# led-cube.net
KiCad netlist of a schematic drawn in Altium Designer
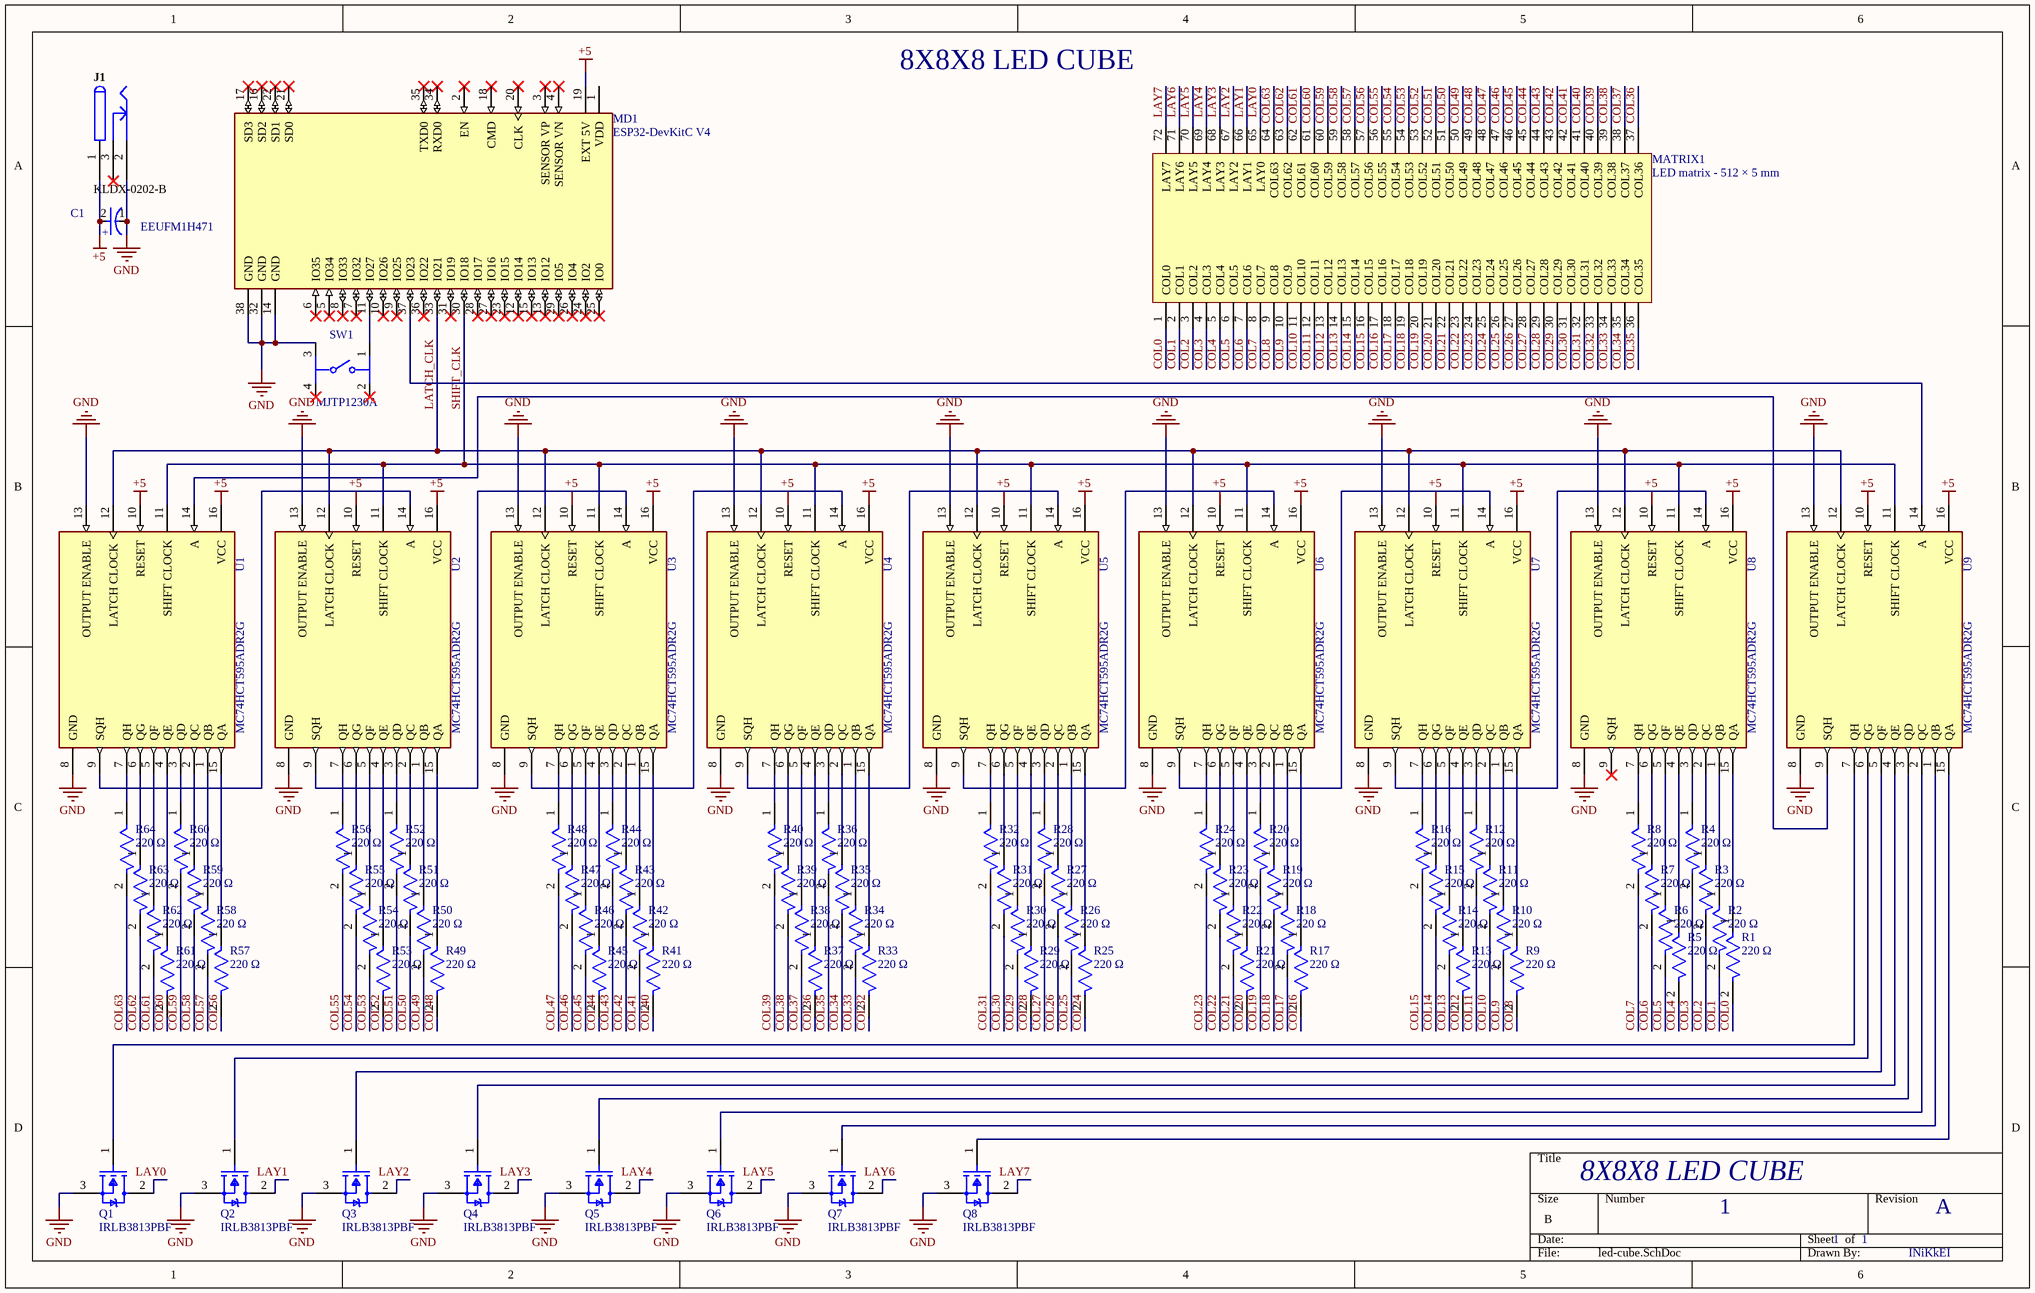
[diagram p0: led-cube.SchDoc]

(export (version "E")
  (design (tool "Eeschema 10.0.6"))
  (components
    (comp (ref "C1")
      (value "EEUFM1H471")
      (footprint "FP-RAD-TH-D_12_5_0_5-L_20-MFG")
      (description "Aluminum Electrolytic Capacitors (Radial Lead Type) 470uF ±20% 50V")
      (fields (field (name "TOLERANCE") "20%") (field (name "VOLTAGE") "50V"))
      (libsource (lib "Altium Content Vault") (part "a00bbbee19879c290e62620ae7e47b1"))
    )
    (comp (ref "J1")
      (value "KLDX-0202-B")
      (footprint "KYCN-KLDX-0202-B_V")
      (description "3 Conductor Power Jack, 2 break 2 aux contacts")
      (libsource (lib "Altium Content Vault") (part "KYCN-KLDX-0202-B-3"))
    )
    (comp (ref "MATRIX1")
      (value "LED matrix - 512 × 5 mm")
      (footprint "LED-MATRIX-8x8x8")
      (description "LED matrix - 512 × 5 mm - 8x8x8")
      (libsource (lib "led-cube") (part "LED-MATRIX"))
    )
    (comp (ref "MD1")
      (value "ESP32-DevKitC V4")
      (footprint "FP-ESP32-DevKitC_V4-MFG")
      (description "WiFi Development Tools (802.11) ESP32 General Development Kit, ESP32-WROOM-32 on the board")
      (fields
        (field (name "OCTOPART") "https://octopart.com/esp32-devkitc+v4-espressif+systems-107467262")
        (field (name "MANUFACTURER") "Espressif")
      )
      (libsource (lib "Altium Content Vault") (part "5ae961a1152c677524a60dea72d22f3"))
    )
    (comp (ref "Q1")
      (value "IRLB3813PBF")
      (footprint "FP-PG-TO220-3-MFG")
      (description "MOSFET N-CH 30V 260A TO-220AB")
      (fields
        (field (name "OCTOPART") "https://octopart.com/irlb3813pbf-infineon-65874923")
        (field (name "MANUFACTURER") "Infineon")
      )
      (libsource (lib "Altium Content Vault") (part "b09f7f152735e370c1ea22a33fa83d6"))
    )
    (comp (ref "Q2")
      (value "IRLB3813PBF")
      (footprint "FP-PG-TO220-3-MFG")
      (description "MOSFET N-CH 30V 260A TO-220AB")
      (fields
        (field (name "OCTOPART") "https://octopart.com/irlb3813pbf-infineon-65874923")
        (field (name "MANUFACTURER") "Infineon")
      )
      (libsource (lib "Altium Content Vault") (part "b09f7f152735e370c1ea22a33fa83d6"))
    )
    (comp (ref "Q3")
      (value "IRLB3813PBF")
      (footprint "FP-PG-TO220-3-MFG")
      (description "MOSFET N-CH 30V 260A TO-220AB")
      (fields
        (field (name "OCTOPART") "https://octopart.com/irlb3813pbf-infineon-65874923")
        (field (name "MANUFACTURER") "Infineon")
      )
      (libsource (lib "Altium Content Vault") (part "b09f7f152735e370c1ea22a33fa83d6"))
    )
    (comp (ref "Q4")
      (value "IRLB3813PBF")
      (footprint "FP-PG-TO220-3-MFG")
      (description "MOSFET N-CH 30V 260A TO-220AB")
      (fields
        (field (name "OCTOPART") "https://octopart.com/irlb3813pbf-infineon-65874923")
        (field (name "MANUFACTURER") "Infineon")
      )
      (libsource (lib "Altium Content Vault") (part "b09f7f152735e370c1ea22a33fa83d6"))
    )
    (comp (ref "Q5")
      (value "IRLB3813PBF")
      (footprint "FP-PG-TO220-3-MFG")
      (description "MOSFET N-CH 30V 260A TO-220AB")
      (fields
        (field (name "OCTOPART") "https://octopart.com/irlb3813pbf-infineon-65874923")
        (field (name "MANUFACTURER") "Infineon")
      )
      (libsource (lib "Altium Content Vault") (part "b09f7f152735e370c1ea22a33fa83d6"))
    )
    (comp (ref "Q6")
      (value "IRLB3813PBF")
      (footprint "FP-PG-TO220-3-MFG")
      (description "MOSFET N-CH 30V 260A TO-220AB")
      (fields
        (field (name "OCTOPART") "https://octopart.com/irlb3813pbf-infineon-65874923")
        (field (name "MANUFACTURER") "Infineon")
      )
      (libsource (lib "Altium Content Vault") (part "b09f7f152735e370c1ea22a33fa83d6"))
    )
    (comp (ref "Q7")
      (value "IRLB3813PBF")
      (footprint "FP-PG-TO220-3-MFG")
      (description "MOSFET N-CH 30V 260A TO-220AB")
      (fields
        (field (name "OCTOPART") "https://octopart.com/irlb3813pbf-infineon-65874923")
        (field (name "MANUFACTURER") "Infineon")
      )
      (libsource (lib "Altium Content Vault") (part "b09f7f152735e370c1ea22a33fa83d6"))
    )
    (comp (ref "Q8")
      (value "IRLB3813PBF")
      (footprint "FP-PG-TO220-3-MFG")
      (description "MOSFET N-CH 30V 260A TO-220AB")
      (fields
        (field (name "OCTOPART") "https://octopart.com/irlb3813pbf-infineon-65874923")
        (field (name "MANUFACTURER") "Infineon")
      )
      (libsource (lib "Altium Content Vault") (part "b09f7f152735e370c1ea22a33fa83d6"))
    )
    (comp (ref "R1")
      (value "220 Ω")
      (footprint "FP-MBA0204-MFG")
      (description "RES 220 OHM 0.4W 1% AXIAL")
      (fields
        (field (name "MANUFACTURER PART NUMBER") "MBA02040C2200FC100")
        (field (name "OCTOPART") "https://octopart.com/mba02040c2200fc100-vishay-43743094")
      )
      (libsource (lib "Altium Content Vault") (part "1029c3af85768c4190bb7ad29bc67b5"))
    )
    (comp (ref "R2")
      (value "220 Ω")
      (footprint "FP-MBA0204-MFG")
      (description "RES 220 OHM 0.4W 1% AXIAL")
      (fields
        (field (name "MANUFACTURER PART NUMBER") "MBA02040C2200FC100")
        (field (name "OCTOPART") "https://octopart.com/mba02040c2200fc100-vishay-43743094")
      )
      (libsource (lib "Altium Content Vault") (part "1029c3af85768c4190bb7ad29bc67b5"))
    )
    (comp (ref "R3")
      (value "220 Ω")
      (footprint "FP-MBA0204-MFG")
      (description "RES 220 OHM 0.4W 1% AXIAL")
      (fields
        (field (name "MANUFACTURER PART NUMBER") "MBA02040C2200FC100")
        (field (name "OCTOPART") "https://octopart.com/mba02040c2200fc100-vishay-43743094")
      )
      (libsource (lib "Altium Content Vault") (part "1029c3af85768c4190bb7ad29bc67b5"))
    )
    (comp (ref "R4")
      (value "220 Ω")
      (footprint "FP-MBA0204-MFG")
      (description "RES 220 OHM 0.4W 1% AXIAL")
      (fields
        (field (name "MANUFACTURER PART NUMBER") "MBA02040C2200FC100")
        (field (name "OCTOPART") "https://octopart.com/mba02040c2200fc100-vishay-43743094")
      )
      (libsource (lib "Altium Content Vault") (part "1029c3af85768c4190bb7ad29bc67b5"))
    )
    (comp (ref "R5")
      (value "220 Ω")
      (footprint "FP-MBA0204-MFG")
      (description "RES 220 OHM 0.4W 1% AXIAL")
      (fields
        (field (name "MANUFACTURER PART NUMBER") "MBA02040C2200FC100")
        (field (name "OCTOPART") "https://octopart.com/mba02040c2200fc100-vishay-43743094")
      )
      (libsource (lib "Altium Content Vault") (part "1029c3af85768c4190bb7ad29bc67b5"))
    )
    (comp (ref "R6")
      (value "220 Ω")
      (footprint "FP-MBA0204-MFG")
      (description "RES 220 OHM 0.4W 1% AXIAL")
      (fields
        (field (name "MANUFACTURER PART NUMBER") "MBA02040C2200FC100")
        (field (name "OCTOPART") "https://octopart.com/mba02040c2200fc100-vishay-43743094")
      )
      (libsource (lib "Altium Content Vault") (part "1029c3af85768c4190bb7ad29bc67b5"))
    )
    (comp (ref "R7")
      (value "220 Ω")
      (footprint "FP-MBA0204-MFG")
      (description "RES 220 OHM 0.4W 1% AXIAL")
      (fields
        (field (name "MANUFACTURER PART NUMBER") "MBA02040C2200FC100")
        (field (name "OCTOPART") "https://octopart.com/mba02040c2200fc100-vishay-43743094")
      )
      (libsource (lib "Altium Content Vault") (part "1029c3af85768c4190bb7ad29bc67b5"))
    )
    (comp (ref "R8")
      (value "220 Ω")
      (footprint "FP-MBA0204-MFG")
      (description "RES 220 OHM 0.4W 1% AXIAL")
      (fields
        (field (name "MANUFACTURER PART NUMBER") "MBA02040C2200FC100")
        (field (name "OCTOPART") "https://octopart.com/mba02040c2200fc100-vishay-43743094")
      )
      (libsource (lib "Altium Content Vault") (part "1029c3af85768c4190bb7ad29bc67b5"))
    )
    (comp (ref "R9")
      (value "220 Ω")
      (footprint "FP-MBA0204-MFG")
      (description "RES 220 OHM 0.4W 1% AXIAL")
      (fields
        (field (name "MANUFACTURER PART NUMBER") "MBA02040C2200FC100")
        (field (name "OCTOPART") "https://octopart.com/mba02040c2200fc100-vishay-43743094")
      )
      (libsource (lib "Altium Content Vault") (part "1029c3af85768c4190bb7ad29bc67b5"))
    )
    (comp (ref "R10")
      (value "220 Ω")
      (footprint "FP-MBA0204-MFG")
      (description "RES 220 OHM 0.4W 1% AXIAL")
      (fields
        (field (name "MANUFACTURER PART NUMBER") "MBA02040C2200FC100")
        (field (name "OCTOPART") "https://octopart.com/mba02040c2200fc100-vishay-43743094")
      )
      (libsource (lib "Altium Content Vault") (part "1029c3af85768c4190bb7ad29bc67b5"))
    )
    (comp (ref "R11")
      (value "220 Ω")
      (footprint "FP-MBA0204-MFG")
      (description "RES 220 OHM 0.4W 1% AXIAL")
      (fields
        (field (name "MANUFACTURER PART NUMBER") "MBA02040C2200FC100")
        (field (name "OCTOPART") "https://octopart.com/mba02040c2200fc100-vishay-43743094")
      )
      (libsource (lib "Altium Content Vault") (part "1029c3af85768c4190bb7ad29bc67b5"))
    )
    (comp (ref "R12")
      (value "220 Ω")
      (footprint "FP-MBA0204-MFG")
      (description "RES 220 OHM 0.4W 1% AXIAL")
      (fields
        (field (name "MANUFACTURER PART NUMBER") "MBA02040C2200FC100")
        (field (name "OCTOPART") "https://octopart.com/mba02040c2200fc100-vishay-43743094")
      )
      (libsource (lib "Altium Content Vault") (part "1029c3af85768c4190bb7ad29bc67b5"))
    )
    (comp (ref "R13")
      (value "220 Ω")
      (footprint "FP-MBA0204-MFG")
      (description "RES 220 OHM 0.4W 1% AXIAL")
      (fields
        (field (name "MANUFACTURER PART NUMBER") "MBA02040C2200FC100")
        (field (name "OCTOPART") "https://octopart.com/mba02040c2200fc100-vishay-43743094")
      )
      (libsource (lib "Altium Content Vault") (part "1029c3af85768c4190bb7ad29bc67b5"))
    )
    (comp (ref "R14")
      (value "220 Ω")
      (footprint "FP-MBA0204-MFG")
      (description "RES 220 OHM 0.4W 1% AXIAL")
      (fields
        (field (name "MANUFACTURER PART NUMBER") "MBA02040C2200FC100")
        (field (name "OCTOPART") "https://octopart.com/mba02040c2200fc100-vishay-43743094")
      )
      (libsource (lib "Altium Content Vault") (part "1029c3af85768c4190bb7ad29bc67b5"))
    )
    (comp (ref "R15")
      (value "220 Ω")
      (footprint "FP-MBA0204-MFG")
      (description "RES 220 OHM 0.4W 1% AXIAL")
      (fields
        (field (name "MANUFACTURER PART NUMBER") "MBA02040C2200FC100")
        (field (name "OCTOPART") "https://octopart.com/mba02040c2200fc100-vishay-43743094")
      )
      (libsource (lib "Altium Content Vault") (part "1029c3af85768c4190bb7ad29bc67b5"))
    )
    (comp (ref "R16")
      (value "220 Ω")
      (footprint "FP-MBA0204-MFG")
      (description "RES 220 OHM 0.4W 1% AXIAL")
      (fields
        (field (name "MANUFACTURER PART NUMBER") "MBA02040C2200FC100")
        (field (name "OCTOPART") "https://octopart.com/mba02040c2200fc100-vishay-43743094")
      )
      (libsource (lib "Altium Content Vault") (part "1029c3af85768c4190bb7ad29bc67b5"))
    )
    (comp (ref "R17")
      (value "220 Ω")
      (footprint "FP-MBA0204-MFG")
      (description "RES 220 OHM 0.4W 1% AXIAL")
      (fields
        (field (name "MANUFACTURER PART NUMBER") "MBA02040C2200FC100")
        (field (name "OCTOPART") "https://octopart.com/mba02040c2200fc100-vishay-43743094")
      )
      (libsource (lib "Altium Content Vault") (part "1029c3af85768c4190bb7ad29bc67b5"))
    )
    (comp (ref "R18")
      (value "220 Ω")
      (footprint "FP-MBA0204-MFG")
      (description "RES 220 OHM 0.4W 1% AXIAL")
      (fields
        (field (name "MANUFACTURER PART NUMBER") "MBA02040C2200FC100")
        (field (name "OCTOPART") "https://octopart.com/mba02040c2200fc100-vishay-43743094")
      )
      (libsource (lib "Altium Content Vault") (part "1029c3af85768c4190bb7ad29bc67b5"))
    )
    (comp (ref "R19")
      (value "220 Ω")
      (footprint "FP-MBA0204-MFG")
      (description "RES 220 OHM 0.4W 1% AXIAL")
      (fields
        (field (name "MANUFACTURER PART NUMBER") "MBA02040C2200FC100")
        (field (name "OCTOPART") "https://octopart.com/mba02040c2200fc100-vishay-43743094")
      )
      (libsource (lib "Altium Content Vault") (part "1029c3af85768c4190bb7ad29bc67b5"))
    )
    (comp (ref "R20")
      (value "220 Ω")
      (footprint "FP-MBA0204-MFG")
      (description "RES 220 OHM 0.4W 1% AXIAL")
      (fields
        (field (name "MANUFACTURER PART NUMBER") "MBA02040C2200FC100")
        (field (name "OCTOPART") "https://octopart.com/mba02040c2200fc100-vishay-43743094")
      )
      (libsource (lib "Altium Content Vault") (part "1029c3af85768c4190bb7ad29bc67b5"))
    )
    (comp (ref "R21")
      (value "220 Ω")
      (footprint "FP-MBA0204-MFG")
      (description "RES 220 OHM 0.4W 1% AXIAL")
      (fields
        (field (name "MANUFACTURER PART NUMBER") "MBA02040C2200FC100")
        (field (name "OCTOPART") "https://octopart.com/mba02040c2200fc100-vishay-43743094")
      )
      (libsource (lib "Altium Content Vault") (part "1029c3af85768c4190bb7ad29bc67b5"))
    )
    (comp (ref "R22")
      (value "220 Ω")
      (footprint "FP-MBA0204-MFG")
      (description "RES 220 OHM 0.4W 1% AXIAL")
      (fields
        (field (name "MANUFACTURER PART NUMBER") "MBA02040C2200FC100")
        (field (name "OCTOPART") "https://octopart.com/mba02040c2200fc100-vishay-43743094")
      )
      (libsource (lib "Altium Content Vault") (part "1029c3af85768c4190bb7ad29bc67b5"))
    )
    (comp (ref "R23")
      (value "220 Ω")
      (footprint "FP-MBA0204-MFG")
      (description "RES 220 OHM 0.4W 1% AXIAL")
      (fields
        (field (name "MANUFACTURER PART NUMBER") "MBA02040C2200FC100")
        (field (name "OCTOPART") "https://octopart.com/mba02040c2200fc100-vishay-43743094")
      )
      (libsource (lib "Altium Content Vault") (part "1029c3af85768c4190bb7ad29bc67b5"))
    )
    (comp (ref "R24")
      (value "220 Ω")
      (footprint "FP-MBA0204-MFG")
      (description "RES 220 OHM 0.4W 1% AXIAL")
      (fields
        (field (name "MANUFACTURER PART NUMBER") "MBA02040C2200FC100")
        (field (name "OCTOPART") "https://octopart.com/mba02040c2200fc100-vishay-43743094")
      )
      (libsource (lib "Altium Content Vault") (part "1029c3af85768c4190bb7ad29bc67b5"))
    )
    (comp (ref "R25")
      (value "220 Ω")
      (footprint "FP-MBA0204-MFG")
      (description "RES 220 OHM 0.4W 1% AXIAL")
      (fields
        (field (name "MANUFACTURER PART NUMBER") "MBA02040C2200FC100")
        (field (name "OCTOPART") "https://octopart.com/mba02040c2200fc100-vishay-43743094")
      )
      (libsource (lib "Altium Content Vault") (part "1029c3af85768c4190bb7ad29bc67b5"))
    )
    (comp (ref "R26")
      (value "220 Ω")
      (footprint "FP-MBA0204-MFG")
      (description "RES 220 OHM 0.4W 1% AXIAL")
      (fields
        (field (name "MANUFACTURER PART NUMBER") "MBA02040C2200FC100")
        (field (name "OCTOPART") "https://octopart.com/mba02040c2200fc100-vishay-43743094")
      )
      (libsource (lib "Altium Content Vault") (part "1029c3af85768c4190bb7ad29bc67b5"))
    )
    (comp (ref "R27")
      (value "220 Ω")
      (footprint "FP-MBA0204-MFG")
      (description "RES 220 OHM 0.4W 1% AXIAL")
      (fields
        (field (name "MANUFACTURER PART NUMBER") "MBA02040C2200FC100")
        (field (name "OCTOPART") "https://octopart.com/mba02040c2200fc100-vishay-43743094")
      )
      (libsource (lib "Altium Content Vault") (part "1029c3af85768c4190bb7ad29bc67b5"))
    )
    (comp (ref "R28")
      (value "220 Ω")
      (footprint "FP-MBA0204-MFG")
      (description "RES 220 OHM 0.4W 1% AXIAL")
      (fields
        (field (name "MANUFACTURER PART NUMBER") "MBA02040C2200FC100")
        (field (name "OCTOPART") "https://octopart.com/mba02040c2200fc100-vishay-43743094")
      )
      (libsource (lib "Altium Content Vault") (part "1029c3af85768c4190bb7ad29bc67b5"))
    )
    (comp (ref "R29")
      (value "220 Ω")
      (footprint "FP-MBA0204-MFG")
      (description "RES 220 OHM 0.4W 1% AXIAL")
      (fields
        (field (name "MANUFACTURER PART NUMBER") "MBA02040C2200FC100")
        (field (name "OCTOPART") "https://octopart.com/mba02040c2200fc100-vishay-43743094")
      )
      (libsource (lib "Altium Content Vault") (part "1029c3af85768c4190bb7ad29bc67b5"))
    )
    (comp (ref "R30")
      (value "220 Ω")
      (footprint "FP-MBA0204-MFG")
      (description "RES 220 OHM 0.4W 1% AXIAL")
      (fields
        (field (name "MANUFACTURER PART NUMBER") "MBA02040C2200FC100")
        (field (name "OCTOPART") "https://octopart.com/mba02040c2200fc100-vishay-43743094")
      )
      (libsource (lib "Altium Content Vault") (part "1029c3af85768c4190bb7ad29bc67b5"))
    )
    (comp (ref "R31")
      (value "220 Ω")
      (footprint "FP-MBA0204-MFG")
      (description "RES 220 OHM 0.4W 1% AXIAL")
      (fields
        (field (name "MANUFACTURER PART NUMBER") "MBA02040C2200FC100")
        (field (name "OCTOPART") "https://octopart.com/mba02040c2200fc100-vishay-43743094")
      )
      (libsource (lib "Altium Content Vault") (part "1029c3af85768c4190bb7ad29bc67b5"))
    )
    (comp (ref "R32")
      (value "220 Ω")
      (footprint "FP-MBA0204-MFG")
      (description "RES 220 OHM 0.4W 1% AXIAL")
      (fields
        (field (name "MANUFACTURER PART NUMBER") "MBA02040C2200FC100")
        (field (name "OCTOPART") "https://octopart.com/mba02040c2200fc100-vishay-43743094")
      )
      (libsource (lib "Altium Content Vault") (part "1029c3af85768c4190bb7ad29bc67b5"))
    )
    (comp (ref "R33")
      (value "220 Ω")
      (footprint "FP-MBA0204-MFG")
      (description "RES 220 OHM 0.4W 1% AXIAL")
      (fields
        (field (name "MANUFACTURER PART NUMBER") "MBA02040C2200FC100")
        (field (name "OCTOPART") "https://octopart.com/mba02040c2200fc100-vishay-43743094")
      )
      (libsource (lib "Altium Content Vault") (part "1029c3af85768c4190bb7ad29bc67b5"))
    )
    (comp (ref "R34")
      (value "220 Ω")
      (footprint "FP-MBA0204-MFG")
      (description "RES 220 OHM 0.4W 1% AXIAL")
      (fields
        (field (name "MANUFACTURER PART NUMBER") "MBA02040C2200FC100")
        (field (name "OCTOPART") "https://octopart.com/mba02040c2200fc100-vishay-43743094")
      )
      (libsource (lib "Altium Content Vault") (part "1029c3af85768c4190bb7ad29bc67b5"))
    )
    (comp (ref "R35")
      (value "220 Ω")
      (footprint "FP-MBA0204-MFG")
      (description "RES 220 OHM 0.4W 1% AXIAL")
      (fields
        (field (name "MANUFACTURER PART NUMBER") "MBA02040C2200FC100")
        (field (name "OCTOPART") "https://octopart.com/mba02040c2200fc100-vishay-43743094")
      )
      (libsource (lib "Altium Content Vault") (part "1029c3af85768c4190bb7ad29bc67b5"))
    )
    (comp (ref "R36")
      (value "220 Ω")
      (footprint "FP-MBA0204-MFG")
      (description "RES 220 OHM 0.4W 1% AXIAL")
      (fields
        (field (name "MANUFACTURER PART NUMBER") "MBA02040C2200FC100")
        (field (name "OCTOPART") "https://octopart.com/mba02040c2200fc100-vishay-43743094")
      )
      (libsource (lib "Altium Content Vault") (part "1029c3af85768c4190bb7ad29bc67b5"))
    )
    (comp (ref "R37")
      (value "220 Ω")
      (footprint "FP-MBA0204-MFG")
      (description "RES 220 OHM 0.4W 1% AXIAL")
      (fields
        (field (name "MANUFACTURER PART NUMBER") "MBA02040C2200FC100")
        (field (name "OCTOPART") "https://octopart.com/mba02040c2200fc100-vishay-43743094")
      )
      (libsource (lib "Altium Content Vault") (part "1029c3af85768c4190bb7ad29bc67b5"))
    )
    (comp (ref "R38")
      (value "220 Ω")
      (footprint "FP-MBA0204-MFG")
      (description "RES 220 OHM 0.4W 1% AXIAL")
      (fields
        (field (name "MANUFACTURER PART NUMBER") "MBA02040C2200FC100")
        (field (name "OCTOPART") "https://octopart.com/mba02040c2200fc100-vishay-43743094")
      )
      (libsource (lib "Altium Content Vault") (part "1029c3af85768c4190bb7ad29bc67b5"))
    )
    (comp (ref "R39")
      (value "220 Ω")
      (footprint "FP-MBA0204-MFG")
      (description "RES 220 OHM 0.4W 1% AXIAL")
      (fields
        (field (name "MANUFACTURER PART NUMBER") "MBA02040C2200FC100")
        (field (name "OCTOPART") "https://octopart.com/mba02040c2200fc100-vishay-43743094")
      )
      (libsource (lib "Altium Content Vault") (part "1029c3af85768c4190bb7ad29bc67b5"))
    )
    (comp (ref "R40")
      (value "220 Ω")
      (footprint "FP-MBA0204-MFG")
      (description "RES 220 OHM 0.4W 1% AXIAL")
      (fields
        (field (name "MANUFACTURER PART NUMBER") "MBA02040C2200FC100")
        (field (name "OCTOPART") "https://octopart.com/mba02040c2200fc100-vishay-43743094")
      )
      (libsource (lib "Altium Content Vault") (part "1029c3af85768c4190bb7ad29bc67b5"))
    )
    (comp (ref "R41")
      (value "220 Ω")
      (footprint "FP-MBA0204-MFG")
      (description "RES 220 OHM 0.4W 1% AXIAL")
      (fields
        (field (name "MANUFACTURER PART NUMBER") "MBA02040C2200FC100")
        (field (name "OCTOPART") "https://octopart.com/mba02040c2200fc100-vishay-43743094")
      )
      (libsource (lib "Altium Content Vault") (part "1029c3af85768c4190bb7ad29bc67b5"))
    )
    (comp (ref "R42")
      (value "220 Ω")
      (footprint "FP-MBA0204-MFG")
      (description "RES 220 OHM 0.4W 1% AXIAL")
      (fields
        (field (name "MANUFACTURER PART NUMBER") "MBA02040C2200FC100")
        (field (name "OCTOPART") "https://octopart.com/mba02040c2200fc100-vishay-43743094")
      )
      (libsource (lib "Altium Content Vault") (part "1029c3af85768c4190bb7ad29bc67b5"))
    )
    (comp (ref "R43")
      (value "220 Ω")
      (footprint "FP-MBA0204-MFG")
      (description "RES 220 OHM 0.4W 1% AXIAL")
      (fields
        (field (name "MANUFACTURER PART NUMBER") "MBA02040C2200FC100")
        (field (name "OCTOPART") "https://octopart.com/mba02040c2200fc100-vishay-43743094")
      )
      (libsource (lib "Altium Content Vault") (part "1029c3af85768c4190bb7ad29bc67b5"))
    )
    (comp (ref "R44")
      (value "220 Ω")
      (footprint "FP-MBA0204-MFG")
      (description "RES 220 OHM 0.4W 1% AXIAL")
      (fields
        (field (name "MANUFACTURER PART NUMBER") "MBA02040C2200FC100")
        (field (name "OCTOPART") "https://octopart.com/mba02040c2200fc100-vishay-43743094")
      )
      (libsource (lib "Altium Content Vault") (part "1029c3af85768c4190bb7ad29bc67b5"))
    )
    (comp (ref "R45")
      (value "220 Ω")
      (footprint "FP-MBA0204-MFG")
      (description "RES 220 OHM 0.4W 1% AXIAL")
      (fields
        (field (name "MANUFACTURER PART NUMBER") "MBA02040C2200FC100")
        (field (name "OCTOPART") "https://octopart.com/mba02040c2200fc100-vishay-43743094")
      )
      (libsource (lib "Altium Content Vault") (part "1029c3af85768c4190bb7ad29bc67b5"))
    )
    (comp (ref "R46")
      (value "220 Ω")
      (footprint "FP-MBA0204-MFG")
      (description "RES 220 OHM 0.4W 1% AXIAL")
      (fields
        (field (name "MANUFACTURER PART NUMBER") "MBA02040C2200FC100")
        (field (name "OCTOPART") "https://octopart.com/mba02040c2200fc100-vishay-43743094")
      )
      (libsource (lib "Altium Content Vault") (part "1029c3af85768c4190bb7ad29bc67b5"))
    )
    (comp (ref "R47")
      (value "220 Ω")
      (footprint "FP-MBA0204-MFG")
      (description "RES 220 OHM 0.4W 1% AXIAL")
      (fields
        (field (name "MANUFACTURER PART NUMBER") "MBA02040C2200FC100")
        (field (name "OCTOPART") "https://octopart.com/mba02040c2200fc100-vishay-43743094")
      )
      (libsource (lib "Altium Content Vault") (part "1029c3af85768c4190bb7ad29bc67b5"))
    )
    (comp (ref "R48")
      (value "220 Ω")
      (footprint "FP-MBA0204-MFG")
      (description "RES 220 OHM 0.4W 1% AXIAL")
      (fields
        (field (name "MANUFACTURER PART NUMBER") "MBA02040C2200FC100")
        (field (name "OCTOPART") "https://octopart.com/mba02040c2200fc100-vishay-43743094")
      )
      (libsource (lib "Altium Content Vault") (part "1029c3af85768c4190bb7ad29bc67b5"))
    )
    (comp (ref "R49")
      (value "220 Ω")
      (footprint "FP-MBA0204-MFG")
      (description "RES 220 OHM 0.4W 1% AXIAL")
      (fields
        (field (name "MANUFACTURER PART NUMBER") "MBA02040C2200FC100")
        (field (name "OCTOPART") "https://octopart.com/mba02040c2200fc100-vishay-43743094")
      )
      (libsource (lib "Altium Content Vault") (part "1029c3af85768c4190bb7ad29bc67b5"))
    )
    (comp (ref "R50")
      (value "220 Ω")
      (footprint "FP-MBA0204-MFG")
      (description "RES 220 OHM 0.4W 1% AXIAL")
      (fields
        (field (name "MANUFACTURER PART NUMBER") "MBA02040C2200FC100")
        (field (name "OCTOPART") "https://octopart.com/mba02040c2200fc100-vishay-43743094")
      )
      (libsource (lib "Altium Content Vault") (part "1029c3af85768c4190bb7ad29bc67b5"))
    )
    (comp (ref "R51")
      (value "220 Ω")
      (footprint "FP-MBA0204-MFG")
      (description "RES 220 OHM 0.4W 1% AXIAL")
      (fields
        (field (name "MANUFACTURER PART NUMBER") "MBA02040C2200FC100")
        (field (name "OCTOPART") "https://octopart.com/mba02040c2200fc100-vishay-43743094")
      )
      (libsource (lib "Altium Content Vault") (part "1029c3af85768c4190bb7ad29bc67b5"))
    )
    (comp (ref "R52")
      (value "220 Ω")
      (footprint "FP-MBA0204-MFG")
      (description "RES 220 OHM 0.4W 1% AXIAL")
      (fields
        (field (name "MANUFACTURER PART NUMBER") "MBA02040C2200FC100")
        (field (name "OCTOPART") "https://octopart.com/mba02040c2200fc100-vishay-43743094")
      )
      (libsource (lib "Altium Content Vault") (part "1029c3af85768c4190bb7ad29bc67b5"))
    )
    (comp (ref "R53")
      (value "220 Ω")
      (footprint "FP-MBA0204-MFG")
      (description "RES 220 OHM 0.4W 1% AXIAL")
      (fields
        (field (name "MANUFACTURER PART NUMBER") "MBA02040C2200FC100")
        (field (name "OCTOPART") "https://octopart.com/mba02040c2200fc100-vishay-43743094")
      )
      (libsource (lib "Altium Content Vault") (part "1029c3af85768c4190bb7ad29bc67b5"))
    )
    (comp (ref "R54")
      (value "220 Ω")
      (footprint "FP-MBA0204-MFG")
      (description "RES 220 OHM 0.4W 1% AXIAL")
      (fields
        (field (name "MANUFACTURER PART NUMBER") "MBA02040C2200FC100")
        (field (name "OCTOPART") "https://octopart.com/mba02040c2200fc100-vishay-43743094")
      )
      (libsource (lib "Altium Content Vault") (part "1029c3af85768c4190bb7ad29bc67b5"))
    )
    (comp (ref "R55")
      (value "220 Ω")
      (footprint "FP-MBA0204-MFG")
      (description "RES 220 OHM 0.4W 1% AXIAL")
      (fields
        (field (name "MANUFACTURER PART NUMBER") "MBA02040C2200FC100")
        (field (name "OCTOPART") "https://octopart.com/mba02040c2200fc100-vishay-43743094")
      )
      (libsource (lib "Altium Content Vault") (part "1029c3af85768c4190bb7ad29bc67b5"))
    )
    (comp (ref "R56")
      (value "220 Ω")
      (footprint "FP-MBA0204-MFG")
      (description "RES 220 OHM 0.4W 1% AXIAL")
      (fields
        (field (name "MANUFACTURER PART NUMBER") "MBA02040C2200FC100")
        (field (name "OCTOPART") "https://octopart.com/mba02040c2200fc100-vishay-43743094")
      )
      (libsource (lib "Altium Content Vault") (part "1029c3af85768c4190bb7ad29bc67b5"))
    )
    (comp (ref "R57")
      (value "220 Ω")
      (footprint "FP-MBA0204-MFG")
      (description "RES 220 OHM 0.4W 1% AXIAL")
      (fields
        (field (name "MANUFACTURER PART NUMBER") "MBA02040C2200FC100")
        (field (name "OCTOPART") "https://octopart.com/mba02040c2200fc100-vishay-43743094")
      )
      (libsource (lib "Altium Content Vault") (part "1029c3af85768c4190bb7ad29bc67b5"))
    )
    (comp (ref "R58")
      (value "220 Ω")
      (footprint "FP-MBA0204-MFG")
      (description "RES 220 OHM 0.4W 1% AXIAL")
      (fields
        (field (name "MANUFACTURER PART NUMBER") "MBA02040C2200FC100")
        (field (name "OCTOPART") "https://octopart.com/mba02040c2200fc100-vishay-43743094")
      )
      (libsource (lib "Altium Content Vault") (part "1029c3af85768c4190bb7ad29bc67b5"))
    )
    (comp (ref "R59")
      (value "220 Ω")
      (footprint "FP-MBA0204-MFG")
      (description "RES 220 OHM 0.4W 1% AXIAL")
      (fields
        (field (name "MANUFACTURER PART NUMBER") "MBA02040C2200FC100")
        (field (name "OCTOPART") "https://octopart.com/mba02040c2200fc100-vishay-43743094")
      )
      (libsource (lib "Altium Content Vault") (part "1029c3af85768c4190bb7ad29bc67b5"))
    )
    (comp (ref "R60")
      (value "220 Ω")
      (footprint "FP-MBA0204-MFG")
      (description "RES 220 OHM 0.4W 1% AXIAL")
      (fields
        (field (name "MANUFACTURER PART NUMBER") "MBA02040C2200FC100")
        (field (name "OCTOPART") "https://octopart.com/mba02040c2200fc100-vishay-43743094")
      )
      (libsource (lib "Altium Content Vault") (part "1029c3af85768c4190bb7ad29bc67b5"))
    )
    (comp (ref "R61")
      (value "220 Ω")
      (footprint "FP-MBA0204-MFG")
      (description "RES 220 OHM 0.4W 1% AXIAL")
      (fields
        (field (name "MANUFACTURER PART NUMBER") "MBA02040C2200FC100")
        (field (name "OCTOPART") "https://octopart.com/mba02040c2200fc100-vishay-43743094")
      )
      (libsource (lib "Altium Content Vault") (part "1029c3af85768c4190bb7ad29bc67b5"))
    )
    (comp (ref "R62")
      (value "220 Ω")
      (footprint "FP-MBA0204-MFG")
      (description "RES 220 OHM 0.4W 1% AXIAL")
      (fields
        (field (name "MANUFACTURER PART NUMBER") "MBA02040C2200FC100")
        (field (name "OCTOPART") "https://octopart.com/mba02040c2200fc100-vishay-43743094")
      )
      (libsource (lib "Altium Content Vault") (part "1029c3af85768c4190bb7ad29bc67b5"))
    )
    (comp (ref "R63")
      (value "220 Ω")
      (footprint "FP-MBA0204-MFG")
      (description "RES 220 OHM 0.4W 1% AXIAL")
      (fields
        (field (name "MANUFACTURER PART NUMBER") "MBA02040C2200FC100")
        (field (name "OCTOPART") "https://octopart.com/mba02040c2200fc100-vishay-43743094")
      )
      (libsource (lib "Altium Content Vault") (part "1029c3af85768c4190bb7ad29bc67b5"))
    )
    (comp (ref "R64")
      (value "220 Ω")
      (footprint "FP-MBA0204-MFG")
      (description "RES 220 OHM 0.4W 1% AXIAL")
      (fields
        (field (name "MANUFACTURER PART NUMBER") "MBA02040C2200FC100")
        (field (name "OCTOPART") "https://octopart.com/mba02040c2200fc100-vishay-43743094")
      )
      (libsource (lib "Altium Content Vault") (part "1029c3af85768c4190bb7ad29bc67b5"))
    )
    (comp (ref "SW1")
      (value "MJTP1230A")
      (footprint "FP-MJTP1230A-MFG")
      (description "SWITCH TACTILE SPST-NO 0.05A 12V")
      (libsource (lib "Altium Content Vault") (part "1adf0dd01260c80cf25a44bfd6b99ba"))
    )
    (comp (ref "U1")
      (value "MC74HCT595ADR2G")
      (footprint "FP-751B-05-MFG")
      (libsource (lib "Altium Content Vault") (part "355c601ec69527b18b491ba11f96b67"))
    )
    (comp (ref "U2")
      (value "MC74HCT595ADR2G")
      (footprint "FP-751B-05-MFG")
      (libsource (lib "Altium Content Vault") (part "355c601ec69527b18b491ba11f96b67"))
    )
    (comp (ref "U3")
      (value "MC74HCT595ADR2G")
      (footprint "FP-751B-05-MFG")
      (libsource (lib "Altium Content Vault") (part "355c601ec69527b18b491ba11f96b67"))
    )
    (comp (ref "U4")
      (value "MC74HCT595ADR2G")
      (footprint "FP-751B-05-MFG")
      (libsource (lib "Altium Content Vault") (part "355c601ec69527b18b491ba11f96b67"))
    )
    (comp (ref "U5")
      (value "MC74HCT595ADR2G")
      (footprint "FP-751B-05-MFG")
      (libsource (lib "Altium Content Vault") (part "355c601ec69527b18b491ba11f96b67"))
    )
    (comp (ref "U6")
      (value "MC74HCT595ADR2G")
      (footprint "FP-751B-05-MFG")
      (libsource (lib "Altium Content Vault") (part "355c601ec69527b18b491ba11f96b67"))
    )
    (comp (ref "U7")
      (value "MC74HCT595ADR2G")
      (footprint "FP-751B-05-MFG")
      (libsource (lib "Altium Content Vault") (part "355c601ec69527b18b491ba11f96b67"))
    )
    (comp (ref "U8")
      (value "MC74HCT595ADR2G")
      (footprint "FP-751B-05-MFG")
      (libsource (lib "Altium Content Vault") (part "355c601ec69527b18b491ba11f96b67"))
    )
    (comp (ref "U9")
      (value "MC74HCT595ADR2G")
      (footprint "FP-751B-05-MFG")
      (libsource (lib "Altium Content Vault") (part "355c601ec69527b18b491ba11f96b67"))
    )
  )
  (nets
    (net (code "1") (name "+5") (class "Default")
      (node (ref "C1") (pin "2") (pinfunction "A_2") (pintype "passive"))
      (node (ref "J1") (pin "1") (pintype "power_in"))
      (node (ref "MD1") (pin "19") (pinfunction "EXT_5V_19") (pintype "power_in"))
      (node (ref "U1") (pin "10") (pinfunction "RESET_10") (pintype "input"))
      (node (ref "U1") (pin "16") (pinfunction "VCC_16") (pintype "power_in"))
      (node (ref "U2") (pin "10") (pinfunction "RESET_10") (pintype "input"))
      (node (ref "U2") (pin "16") (pinfunction "VCC_16") (pintype "power_in"))
      (node (ref "U3") (pin "10") (pinfunction "RESET_10") (pintype "input"))
      (node (ref "U3") (pin "16") (pinfunction "VCC_16") (pintype "power_in"))
      (node (ref "U4") (pin "10") (pinfunction "RESET_10") (pintype "input"))
      (node (ref "U4") (pin "16") (pinfunction "VCC_16") (pintype "power_in"))
      (node (ref "U5") (pin "10") (pinfunction "RESET_10") (pintype "input"))
      (node (ref "U5") (pin "16") (pinfunction "VCC_16") (pintype "power_in"))
      (node (ref "U6") (pin "10") (pinfunction "RESET_10") (pintype "input"))
      (node (ref "U6") (pin "16") (pinfunction "VCC_16") (pintype "power_in"))
      (node (ref "U7") (pin "10") (pinfunction "RESET_10") (pintype "input"))
      (node (ref "U7") (pin "16") (pinfunction "VCC_16") (pintype "power_in"))
      (node (ref "U8") (pin "10") (pinfunction "RESET_10") (pintype "input"))
      (node (ref "U8") (pin "16") (pinfunction "VCC_16") (pintype "power_in"))
      (node (ref "U9") (pin "10") (pinfunction "RESET_10") (pintype "input"))
      (node (ref "U9") (pin "16") (pinfunction "VCC_16") (pintype "power_in"))
    )
    (net (code "2") (name "/COL0") (class "Default")
      (node (ref "MATRIX1") (pin "1") (pinfunction "COL0_1") (pintype "passive"))
      (node (ref "R1") (pin "2") (pinfunction "2_2") (pintype "passive"))
    )
    (net (code "3") (name "/COL1") (class "Default")
      (node (ref "MATRIX1") (pin "2") (pinfunction "COL1_2") (pintype "passive"))
      (node (ref "R2") (pin "2") (pinfunction "2_2") (pintype "passive"))
    )
    (net (code "4") (name "/COL2") (class "Default")
      (node (ref "MATRIX1") (pin "3") (pinfunction "COL2_3") (pintype "passive"))
      (node (ref "R3") (pin "2") (pinfunction "2_2") (pintype "passive"))
    )
    (net (code "5") (name "/COL3") (class "Default")
      (node (ref "MATRIX1") (pin "4") (pinfunction "COL3_4") (pintype "passive"))
      (node (ref "R4") (pin "2") (pinfunction "2_2") (pintype "passive"))
    )
    (net (code "6") (name "/COL4") (class "Default")
      (node (ref "MATRIX1") (pin "5") (pinfunction "COL4_5") (pintype "passive"))
      (node (ref "R5") (pin "2") (pinfunction "2_2") (pintype "passive"))
    )
    (net (code "7") (name "/COL5") (class "Default")
      (node (ref "MATRIX1") (pin "6") (pinfunction "COL5_6") (pintype "passive"))
      (node (ref "R6") (pin "2") (pinfunction "2_2") (pintype "passive"))
    )
    (net (code "8") (name "/COL6") (class "Default")
      (node (ref "MATRIX1") (pin "7") (pinfunction "COL6_7") (pintype "passive"))
      (node (ref "R7") (pin "2") (pinfunction "2_2") (pintype "passive"))
    )
    (net (code "9") (name "/COL7") (class "Default")
      (node (ref "MATRIX1") (pin "8") (pinfunction "COL7_8") (pintype "passive"))
      (node (ref "R8") (pin "2") (pinfunction "2_2") (pintype "passive"))
    )
    (net (code "10") (name "/COL8") (class "Default")
      (node (ref "MATRIX1") (pin "9") (pinfunction "COL8_9") (pintype "passive"))
      (node (ref "R9") (pin "2") (pinfunction "2_2") (pintype "passive"))
    )
    (net (code "11") (name "/COL9") (class "Default")
      (node (ref "MATRIX1") (pin "10") (pinfunction "COL9_10") (pintype "passive"))
      (node (ref "R10") (pin "2") (pinfunction "2_2") (pintype "passive"))
    )
    (net (code "12") (name "/COL10") (class "Default")
      (node (ref "MATRIX1") (pin "11") (pinfunction "COL10_11") (pintype "passive"))
      (node (ref "R11") (pin "2") (pinfunction "2_2") (pintype "passive"))
    )
    (net (code "13") (name "/COL11") (class "Default")
      (node (ref "MATRIX1") (pin "12") (pinfunction "COL11_12") (pintype "passive"))
      (node (ref "R12") (pin "2") (pinfunction "2_2") (pintype "passive"))
    )
    (net (code "14") (name "/COL12") (class "Default")
      (node (ref "MATRIX1") (pin "13") (pinfunction "COL12_13") (pintype "passive"))
      (node (ref "R13") (pin "2") (pinfunction "2_2") (pintype "passive"))
    )
    (net (code "15") (name "/COL13") (class "Default")
      (node (ref "MATRIX1") (pin "14") (pinfunction "COL13_14") (pintype "passive"))
      (node (ref "R14") (pin "2") (pinfunction "2_2") (pintype "passive"))
    )
    (net (code "16") (name "/COL14") (class "Default")
      (node (ref "MATRIX1") (pin "15") (pinfunction "COL14_15") (pintype "passive"))
      (node (ref "R15") (pin "2") (pinfunction "2_2") (pintype "passive"))
    )
    (net (code "17") (name "/COL15") (class "Default")
      (node (ref "MATRIX1") (pin "16") (pinfunction "COL15_16") (pintype "passive"))
      (node (ref "R16") (pin "2") (pinfunction "2_2") (pintype "passive"))
    )
    (net (code "18") (name "/COL16") (class "Default")
      (node (ref "MATRIX1") (pin "17") (pinfunction "COL16_17") (pintype "passive"))
      (node (ref "R17") (pin "2") (pinfunction "2_2") (pintype "passive"))
    )
    (net (code "19") (name "/COL17") (class "Default")
      (node (ref "MATRIX1") (pin "18") (pinfunction "COL17_18") (pintype "passive"))
      (node (ref "R18") (pin "2") (pinfunction "2_2") (pintype "passive"))
    )
    (net (code "20") (name "/COL18") (class "Default")
      (node (ref "MATRIX1") (pin "19") (pinfunction "COL18_19") (pintype "passive"))
      (node (ref "R19") (pin "2") (pinfunction "2_2") (pintype "passive"))
    )
    (net (code "21") (name "/COL19") (class "Default")
      (node (ref "MATRIX1") (pin "20") (pinfunction "COL19_20") (pintype "passive"))
      (node (ref "R20") (pin "2") (pinfunction "2_2") (pintype "passive"))
    )
    (net (code "22") (name "/COL20") (class "Default")
      (node (ref "MATRIX1") (pin "21") (pinfunction "COL20_21") (pintype "passive"))
      (node (ref "R21") (pin "2") (pinfunction "2_2") (pintype "passive"))
    )
    (net (code "23") (name "/COL21") (class "Default")
      (node (ref "MATRIX1") (pin "22") (pinfunction "COL21_22") (pintype "passive"))
      (node (ref "R22") (pin "2") (pinfunction "2_2") (pintype "passive"))
    )
    (net (code "24") (name "/COL22") (class "Default")
      (node (ref "MATRIX1") (pin "23") (pinfunction "COL22_23") (pintype "passive"))
      (node (ref "R23") (pin "2") (pinfunction "2_2") (pintype "passive"))
    )
    (net (code "25") (name "/COL23") (class "Default")
      (node (ref "MATRIX1") (pin "24") (pinfunction "COL23_24") (pintype "passive"))
      (node (ref "R24") (pin "2") (pinfunction "2_2") (pintype "passive"))
    )
    (net (code "26") (name "/COL24") (class "Default")
      (node (ref "MATRIX1") (pin "25") (pinfunction "COL24_25") (pintype "passive"))
      (node (ref "R25") (pin "2") (pinfunction "2_2") (pintype "passive"))
    )
    (net (code "27") (name "/COL25") (class "Default")
      (node (ref "MATRIX1") (pin "26") (pinfunction "COL25_26") (pintype "passive"))
      (node (ref "R26") (pin "2") (pinfunction "2_2") (pintype "passive"))
    )
    (net (code "28") (name "/COL26") (class "Default")
      (node (ref "MATRIX1") (pin "27") (pinfunction "COL26_27") (pintype "passive"))
      (node (ref "R27") (pin "2") (pinfunction "2_2") (pintype "passive"))
    )
    (net (code "29") (name "/COL27") (class "Default")
      (node (ref "MATRIX1") (pin "28") (pinfunction "COL27_28") (pintype "passive"))
      (node (ref "R28") (pin "2") (pinfunction "2_2") (pintype "passive"))
    )
    (net (code "30") (name "/COL28") (class "Default")
      (node (ref "MATRIX1") (pin "29") (pinfunction "COL28_29") (pintype "passive"))
      (node (ref "R29") (pin "2") (pinfunction "2_2") (pintype "passive"))
    )
    (net (code "31") (name "/COL29") (class "Default")
      (node (ref "MATRIX1") (pin "30") (pinfunction "COL29_30") (pintype "passive"))
      (node (ref "R30") (pin "2") (pinfunction "2_2") (pintype "passive"))
    )
    (net (code "32") (name "/COL30") (class "Default")
      (node (ref "MATRIX1") (pin "31") (pinfunction "COL30_31") (pintype "passive"))
      (node (ref "R31") (pin "2") (pinfunction "2_2") (pintype "passive"))
    )
    (net (code "33") (name "/COL31") (class "Default")
      (node (ref "MATRIX1") (pin "32") (pinfunction "COL31_32") (pintype "passive"))
      (node (ref "R32") (pin "2") (pinfunction "2_2") (pintype "passive"))
    )
    (net (code "34") (name "/COL32") (class "Default")
      (node (ref "MATRIX1") (pin "33") (pinfunction "COL32_33") (pintype "passive"))
      (node (ref "R33") (pin "2") (pinfunction "2_2") (pintype "passive"))
    )
    (net (code "35") (name "/COL33") (class "Default")
      (node (ref "MATRIX1") (pin "34") (pinfunction "COL33_34") (pintype "passive"))
      (node (ref "R34") (pin "2") (pinfunction "2_2") (pintype "passive"))
    )
    (net (code "36") (name "/COL34") (class "Default")
      (node (ref "MATRIX1") (pin "35") (pinfunction "COL34_35") (pintype "passive"))
      (node (ref "R35") (pin "2") (pinfunction "2_2") (pintype "passive"))
    )
    (net (code "37") (name "/COL35") (class "Default")
      (node (ref "MATRIX1") (pin "36") (pinfunction "COL35_36") (pintype "passive"))
      (node (ref "R36") (pin "2") (pinfunction "2_2") (pintype "passive"))
    )
    (net (code "38") (name "/COL36") (class "Default")
      (node (ref "MATRIX1") (pin "37") (pinfunction "COL36_37") (pintype "passive"))
      (node (ref "R37") (pin "2") (pinfunction "2_2") (pintype "passive"))
    )
    (net (code "39") (name "/COL37") (class "Default")
      (node (ref "MATRIX1") (pin "38") (pinfunction "COL37_38") (pintype "passive"))
      (node (ref "R38") (pin "2") (pinfunction "2_2") (pintype "passive"))
    )
    (net (code "40") (name "/COL38") (class "Default")
      (node (ref "MATRIX1") (pin "39") (pinfunction "COL38_39") (pintype "passive"))
      (node (ref "R39") (pin "2") (pinfunction "2_2") (pintype "passive"))
    )
    (net (code "41") (name "/COL39") (class "Default")
      (node (ref "MATRIX1") (pin "40") (pinfunction "COL39_40") (pintype "passive"))
      (node (ref "R40") (pin "2") (pinfunction "2_2") (pintype "passive"))
    )
    (net (code "42") (name "/COL40") (class "Default")
      (node (ref "MATRIX1") (pin "41") (pinfunction "COL40_41") (pintype "passive"))
      (node (ref "R41") (pin "2") (pinfunction "2_2") (pintype "passive"))
    )
    (net (code "43") (name "/COL41") (class "Default")
      (node (ref "MATRIX1") (pin "42") (pinfunction "COL41_42") (pintype "passive"))
      (node (ref "R42") (pin "2") (pinfunction "2_2") (pintype "passive"))
    )
    (net (code "44") (name "/COL42") (class "Default")
      (node (ref "MATRIX1") (pin "43") (pinfunction "COL42_43") (pintype "passive"))
      (node (ref "R43") (pin "2") (pinfunction "2_2") (pintype "passive"))
    )
    (net (code "45") (name "/COL43") (class "Default")
      (node (ref "MATRIX1") (pin "44") (pinfunction "COL43_44") (pintype "passive"))
      (node (ref "R44") (pin "2") (pinfunction "2_2") (pintype "passive"))
    )
    (net (code "46") (name "/COL44") (class "Default")
      (node (ref "MATRIX1") (pin "45") (pinfunction "COL44_45") (pintype "passive"))
      (node (ref "R45") (pin "2") (pinfunction "2_2") (pintype "passive"))
    )
    (net (code "47") (name "/COL45") (class "Default")
      (node (ref "MATRIX1") (pin "46") (pinfunction "COL45_46") (pintype "passive"))
      (node (ref "R46") (pin "2") (pinfunction "2_2") (pintype "passive"))
    )
    (net (code "48") (name "/COL46") (class "Default")
      (node (ref "MATRIX1") (pin "47") (pinfunction "COL46_47") (pintype "passive"))
      (node (ref "R47") (pin "2") (pinfunction "2_2") (pintype "passive"))
    )
    (net (code "49") (name "/COL47") (class "Default")
      (node (ref "MATRIX1") (pin "48") (pinfunction "COL47_48") (pintype "passive"))
      (node (ref "R48") (pin "2") (pinfunction "2_2") (pintype "passive"))
    )
    (net (code "50") (name "/COL48") (class "Default")
      (node (ref "MATRIX1") (pin "49") (pinfunction "COL48_49") (pintype "passive"))
      (node (ref "R49") (pin "2") (pinfunction "2_2") (pintype "passive"))
    )
    (net (code "51") (name "/COL49") (class "Default")
      (node (ref "MATRIX1") (pin "50") (pinfunction "COL49_50") (pintype "passive"))
      (node (ref "R50") (pin "2") (pinfunction "2_2") (pintype "passive"))
    )
    (net (code "52") (name "/COL50") (class "Default")
      (node (ref "MATRIX1") (pin "51") (pinfunction "COL50_51") (pintype "passive"))
      (node (ref "R51") (pin "2") (pinfunction "2_2") (pintype "passive"))
    )
    (net (code "53") (name "/COL51") (class "Default")
      (node (ref "MATRIX1") (pin "52") (pinfunction "COL51_52") (pintype "passive"))
      (node (ref "R52") (pin "2") (pinfunction "2_2") (pintype "passive"))
    )
    (net (code "54") (name "/COL52") (class "Default")
      (node (ref "MATRIX1") (pin "53") (pinfunction "COL52_53") (pintype "passive"))
      (node (ref "R53") (pin "2") (pinfunction "2_2") (pintype "passive"))
    )
    (net (code "55") (name "/COL53") (class "Default")
      (node (ref "MATRIX1") (pin "54") (pinfunction "COL53_54") (pintype "passive"))
      (node (ref "R54") (pin "2") (pinfunction "2_2") (pintype "passive"))
    )
    (net (code "56") (name "/COL54") (class "Default")
      (node (ref "MATRIX1") (pin "55") (pinfunction "COL54_55") (pintype "passive"))
      (node (ref "R55") (pin "2") (pinfunction "2_2") (pintype "passive"))
    )
    (net (code "57") (name "/COL55") (class "Default")
      (node (ref "MATRIX1") (pin "56") (pinfunction "COL55_56") (pintype "passive"))
      (node (ref "R56") (pin "2") (pinfunction "2_2") (pintype "passive"))
    )
    (net (code "58") (name "/COL56") (class "Default")
      (node (ref "MATRIX1") (pin "57") (pinfunction "COL56_57") (pintype "passive"))
      (node (ref "R57") (pin "2") (pinfunction "2_2") (pintype "passive"))
    )
    (net (code "59") (name "/COL57") (class "Default")
      (node (ref "MATRIX1") (pin "58") (pinfunction "COL57_58") (pintype "passive"))
      (node (ref "R58") (pin "2") (pinfunction "2_2") (pintype "passive"))
    )
    (net (code "60") (name "/COL58") (class "Default")
      (node (ref "MATRIX1") (pin "59") (pinfunction "COL58_59") (pintype "passive"))
      (node (ref "R59") (pin "2") (pinfunction "2_2") (pintype "passive"))
    )
    (net (code "61") (name "/COL59") (class "Default")
      (node (ref "MATRIX1") (pin "60") (pinfunction "COL59_60") (pintype "passive"))
      (node (ref "R60") (pin "2") (pinfunction "2_2") (pintype "passive"))
    )
    (net (code "62") (name "/COL60") (class "Default")
      (node (ref "MATRIX1") (pin "61") (pinfunction "COL60_61") (pintype "passive"))
      (node (ref "R61") (pin "2") (pinfunction "2_2") (pintype "passive"))
    )
    (net (code "63") (name "/COL61") (class "Default")
      (node (ref "MATRIX1") (pin "62") (pinfunction "COL61_62") (pintype "passive"))
      (node (ref "R62") (pin "2") (pinfunction "2_2") (pintype "passive"))
    )
    (net (code "64") (name "/COL62") (class "Default")
      (node (ref "MATRIX1") (pin "63") (pinfunction "COL62_63") (pintype "passive"))
      (node (ref "R63") (pin "2") (pinfunction "2_2") (pintype "passive"))
    )
    (net (code "65") (name "/COL63") (class "Default")
      (node (ref "MATRIX1") (pin "64") (pinfunction "COL63_64") (pintype "passive"))
      (node (ref "R64") (pin "2") (pinfunction "2_2") (pintype "passive"))
    )
    (net (code "66") (name "/LATCH_CLK") (class "Default")
      (node (ref "MD1") (pin "33") (pinfunction "IO21_33") (pintype "bidirectional"))
      (node (ref "U1") (pin "12") (pinfunction "LATCH_CLOCK_12") (pintype "passive"))
      (node (ref "U2") (pin "12") (pinfunction "LATCH_CLOCK_12") (pintype "passive"))
      (node (ref "U3") (pin "12") (pinfunction "LATCH_CLOCK_12") (pintype "passive"))
      (node (ref "U4") (pin "12") (pinfunction "LATCH_CLOCK_12") (pintype "passive"))
      (node (ref "U5") (pin "12") (pinfunction "LATCH_CLOCK_12") (pintype "passive"))
      (node (ref "U6") (pin "12") (pinfunction "LATCH_CLOCK_12") (pintype "passive"))
      (node (ref "U7") (pin "12") (pinfunction "LATCH_CLOCK_12") (pintype "passive"))
      (node (ref "U8") (pin "12") (pinfunction "LATCH_CLOCK_12") (pintype "passive"))
      (node (ref "U9") (pin "12") (pinfunction "LATCH_CLOCK_12") (pintype "passive"))
    )
    (net (code "67") (name "/LAY0") (class "Default")
      (node (ref "MATRIX1") (pin "65") (pinfunction "LAY0_65") (pintype "passive"))
      (node (ref "Q1") (pin "2") (pinfunction "D_2") (pintype "passive"))
    )
    (net (code "68") (name "/LAY1") (class "Default")
      (node (ref "MATRIX1") (pin "66") (pinfunction "LAY1_66") (pintype "passive"))
      (node (ref "Q2") (pin "2") (pinfunction "D_2") (pintype "passive"))
    )
    (net (code "69") (name "/LAY2") (class "Default")
      (node (ref "MATRIX1") (pin "67") (pinfunction "LAY2_67") (pintype "passive"))
      (node (ref "Q3") (pin "2") (pinfunction "D_2") (pintype "passive"))
    )
    (net (code "70") (name "/LAY3") (class "Default")
      (node (ref "MATRIX1") (pin "68") (pinfunction "LAY3_68") (pintype "passive"))
      (node (ref "Q4") (pin "2") (pinfunction "D_2") (pintype "passive"))
    )
    (net (code "71") (name "/LAY4") (class "Default")
      (node (ref "MATRIX1") (pin "69") (pinfunction "LAY4_69") (pintype "passive"))
      (node (ref "Q5") (pin "2") (pinfunction "D_2") (pintype "passive"))
    )
    (net (code "72") (name "/LAY5") (class "Default")
      (node (ref "MATRIX1") (pin "70") (pinfunction "LAY5_70") (pintype "passive"))
      (node (ref "Q6") (pin "2") (pinfunction "D_2") (pintype "passive"))
    )
    (net (code "73") (name "/LAY6") (class "Default")
      (node (ref "MATRIX1") (pin "71") (pinfunction "LAY6_71") (pintype "passive"))
      (node (ref "Q7") (pin "2") (pinfunction "D_2") (pintype "passive"))
    )
    (net (code "74") (name "/LAY7") (class "Default")
      (node (ref "MATRIX1") (pin "72") (pinfunction "LAY7_72") (pintype "passive"))
      (node (ref "Q8") (pin "2") (pinfunction "D_2") (pintype "passive"))
    )
    (net (code "75") (name "/SHIFT_CLK") (class "Default")
      (node (ref "MD1") (pin "30") (pinfunction "IO18_30") (pintype "bidirectional"))
      (node (ref "U1") (pin "11") (pinfunction "SHIFT_CLOCK_11") (pintype "passive"))
      (node (ref "U2") (pin "11") (pinfunction "SHIFT_CLOCK_11") (pintype "passive"))
      (node (ref "U3") (pin "11") (pinfunction "SHIFT_CLOCK_11") (pintype "passive"))
      (node (ref "U4") (pin "11") (pinfunction "SHIFT_CLOCK_11") (pintype "passive"))
      (node (ref "U5") (pin "11") (pinfunction "SHIFT_CLOCK_11") (pintype "passive"))
      (node (ref "U6") (pin "11") (pinfunction "SHIFT_CLOCK_11") (pintype "passive"))
      (node (ref "U7") (pin "11") (pinfunction "SHIFT_CLOCK_11") (pintype "passive"))
      (node (ref "U8") (pin "11") (pinfunction "SHIFT_CLOCK_11") (pintype "passive"))
      (node (ref "U9") (pin "11") (pinfunction "SHIFT_CLOCK_11") (pintype "passive"))
    )
    (net (code "76") (name "GND") (class "Default")
      (node (ref "C1") (pin "1") (pinfunction "C_1") (pintype "passive"))
      (node (ref "J1") (pin "2") (pintype "power_in"))
      (node (ref "MD1") (pin "14") (pinfunction "GND_14") (pintype "power_in"))
      (node (ref "MD1") (pin "32") (pinfunction "GND_32") (pintype "power_in"))
      (node (ref "MD1") (pin "38") (pinfunction "GND_38") (pintype "power_in"))
      (node (ref "Q1") (pin "3") (pinfunction "S_3") (pintype "passive"))
      (node (ref "Q2") (pin "3") (pinfunction "S_3") (pintype "passive"))
      (node (ref "Q3") (pin "3") (pinfunction "S_3") (pintype "passive"))
      (node (ref "Q4") (pin "3") (pinfunction "S_3") (pintype "passive"))
      (node (ref "Q5") (pin "3") (pinfunction "S_3") (pintype "passive"))
      (node (ref "Q6") (pin "3") (pinfunction "S_3") (pintype "passive"))
      (node (ref "Q7") (pin "3") (pinfunction "S_3") (pintype "passive"))
      (node (ref "Q8") (pin "3") (pinfunction "S_3") (pintype "passive"))
      (node (ref "SW1") (pin "3") (pinfunction "3_3") (pintype "passive"))
      (node (ref "U1") (pin "13") (pinfunction "OUTPUT_ENABLE_13") (pintype "input"))
      (node (ref "U1") (pin "8") (pinfunction "GND_8") (pintype "power_in"))
      (node (ref "U2") (pin "13") (pinfunction "OUTPUT_ENABLE_13") (pintype "input"))
      (node (ref "U2") (pin "8") (pinfunction "GND_8") (pintype "power_in"))
      (node (ref "U3") (pin "13") (pinfunction "OUTPUT_ENABLE_13") (pintype "input"))
      (node (ref "U3") (pin "8") (pinfunction "GND_8") (pintype "power_in"))
      (node (ref "U4") (pin "13") (pinfunction "OUTPUT_ENABLE_13") (pintype "input"))
      (node (ref "U4") (pin "8") (pinfunction "GND_8") (pintype "power_in"))
      (node (ref "U5") (pin "13") (pinfunction "OUTPUT_ENABLE_13") (pintype "input"))
      (node (ref "U5") (pin "8") (pinfunction "GND_8") (pintype "power_in"))
      (node (ref "U6") (pin "13") (pinfunction "OUTPUT_ENABLE_13") (pintype "input"))
      (node (ref "U6") (pin "8") (pinfunction "GND_8") (pintype "power_in"))
      (node (ref "U7") (pin "13") (pinfunction "OUTPUT_ENABLE_13") (pintype "input"))
      (node (ref "U7") (pin "8") (pinfunction "GND_8") (pintype "power_in"))
      (node (ref "U8") (pin "13") (pinfunction "OUTPUT_ENABLE_13") (pintype "input"))
      (node (ref "U8") (pin "8") (pinfunction "GND_8") (pintype "power_in"))
      (node (ref "U9") (pin "13") (pinfunction "OUTPUT_ENABLE_13") (pintype "input"))
      (node (ref "U9") (pin "8") (pinfunction "GND_8") (pintype "power_in"))
    )
    (net (code "77") (name "Net-(MD1-IO23)") (class "Default")
      (node (ref "MD1") (pin "37") (pinfunction "IO23_37") (pintype "bidirectional"))
      (node (ref "U9") (pin "14") (pinfunction "A_14") (pintype "input"))
    )
    (net (code "78") (name "Net-(MD1-IO27)") (class "Default")
      (node (ref "MD1") (pin "11") (pinfunction "IO27_11") (pintype "bidirectional"))
      (node (ref "SW1") (pin "1") (pinfunction "1_1") (pintype "passive"))
    )
    (net (code "79") (name "Net-(Q1-G)") (class "Default")
      (node (ref "Q1") (pin "1") (pinfunction "G_1") (pintype "passive"))
      (node (ref "U9") (pin "7") (pinfunction "QH_7") (pintype "output"))
    )
    (net (code "80") (name "Net-(Q2-G)") (class "Default")
      (node (ref "Q2") (pin "1") (pinfunction "G_1") (pintype "passive"))
      (node (ref "U9") (pin "6") (pinfunction "QG_6") (pintype "output"))
    )
    (net (code "81") (name "Net-(Q3-G)") (class "Default")
      (node (ref "Q3") (pin "1") (pinfunction "G_1") (pintype "passive"))
      (node (ref "U9") (pin "5") (pinfunction "QF_5") (pintype "output"))
    )
    (net (code "82") (name "Net-(Q4-G)") (class "Default")
      (node (ref "Q4") (pin "1") (pinfunction "G_1") (pintype "passive"))
      (node (ref "U9") (pin "4") (pinfunction "QE_4") (pintype "output"))
    )
    (net (code "83") (name "Net-(Q5-G)") (class "Default")
      (node (ref "Q5") (pin "1") (pinfunction "G_1") (pintype "passive"))
      (node (ref "U9") (pin "3") (pinfunction "QD_3") (pintype "output"))
    )
    (net (code "84") (name "Net-(Q6-G)") (class "Default")
      (node (ref "Q6") (pin "1") (pinfunction "G_1") (pintype "passive"))
      (node (ref "U9") (pin "2") (pinfunction "QC_2") (pintype "output"))
    )
    (net (code "85") (name "Net-(Q7-G)") (class "Default")
      (node (ref "Q7") (pin "1") (pinfunction "G_1") (pintype "passive"))
      (node (ref "U9") (pin "1") (pinfunction "QB_1") (pintype "output"))
    )
    (net (code "86") (name "Net-(Q8-G)") (class "Default")
      (node (ref "Q8") (pin "1") (pinfunction "G_1") (pintype "passive"))
      (node (ref "U9") (pin "15") (pinfunction "QA_15") (pintype "output"))
    )
    (net (code "87") (name "Net-(U1-A)") (class "Default")
      (node (ref "U1") (pin "14") (pinfunction "A_14") (pintype "input"))
      (node (ref "U9") (pin "9") (pinfunction "SQH_9") (pintype "output"))
    )
    (net (code "88") (name "Net-(U1-QA)") (class "Default")
      (node (ref "R57") (pin "1") (pinfunction "1_1") (pintype "passive"))
      (node (ref "U1") (pin "15") (pinfunction "QA_15") (pintype "output"))
    )
    (net (code "89") (name "Net-(U1-QB)") (class "Default")
      (node (ref "R58") (pin "1") (pinfunction "1_1") (pintype "passive"))
      (node (ref "U1") (pin "1") (pinfunction "QB_1") (pintype "output"))
    )
    (net (code "90") (name "Net-(U1-QC)") (class "Default")
      (node (ref "R59") (pin "1") (pinfunction "1_1") (pintype "passive"))
      (node (ref "U1") (pin "2") (pinfunction "QC_2") (pintype "output"))
    )
    (net (code "91") (name "Net-(U1-QD)") (class "Default")
      (node (ref "R60") (pin "1") (pinfunction "1_1") (pintype "passive"))
      (node (ref "U1") (pin "3") (pinfunction "QD_3") (pintype "output"))
    )
    (net (code "92") (name "Net-(U1-QE)") (class "Default")
      (node (ref "R61") (pin "1") (pinfunction "1_1") (pintype "passive"))
      (node (ref "U1") (pin "4") (pinfunction "QE_4") (pintype "output"))
    )
    (net (code "93") (name "Net-(U1-QF)") (class "Default")
      (node (ref "R62") (pin "1") (pinfunction "1_1") (pintype "passive"))
      (node (ref "U1") (pin "5") (pinfunction "QF_5") (pintype "output"))
    )
    (net (code "94") (name "Net-(U1-QG)") (class "Default")
      (node (ref "R63") (pin "1") (pinfunction "1_1") (pintype "passive"))
      (node (ref "U1") (pin "6") (pinfunction "QG_6") (pintype "output"))
    )
    (net (code "95") (name "Net-(U1-QH)") (class "Default")
      (node (ref "R64") (pin "1") (pinfunction "1_1") (pintype "passive"))
      (node (ref "U1") (pin "7") (pinfunction "QH_7") (pintype "output"))
    )
    (net (code "96") (name "Net-(U1-SQH)") (class "Default")
      (node (ref "U1") (pin "9") (pinfunction "SQH_9") (pintype "output"))
      (node (ref "U2") (pin "14") (pinfunction "A_14") (pintype "input"))
    )
    (net (code "97") (name "Net-(U2-QA)") (class "Default")
      (node (ref "R49") (pin "1") (pinfunction "1_1") (pintype "passive"))
      (node (ref "U2") (pin "15") (pinfunction "QA_15") (pintype "output"))
    )
    (net (code "98") (name "Net-(U2-QB)") (class "Default")
      (node (ref "R50") (pin "1") (pinfunction "1_1") (pintype "passive"))
      (node (ref "U2") (pin "1") (pinfunction "QB_1") (pintype "output"))
    )
    (net (code "99") (name "Net-(U2-QC)") (class "Default")
      (node (ref "R51") (pin "1") (pinfunction "1_1") (pintype "passive"))
      (node (ref "U2") (pin "2") (pinfunction "QC_2") (pintype "output"))
    )
    (net (code "100") (name "Net-(U2-QD)") (class "Default")
      (node (ref "R52") (pin "1") (pinfunction "1_1") (pintype "passive"))
      (node (ref "U2") (pin "3") (pinfunction "QD_3") (pintype "output"))
    )
    (net (code "101") (name "Net-(U2-QE)") (class "Default")
      (node (ref "R53") (pin "1") (pinfunction "1_1") (pintype "passive"))
      (node (ref "U2") (pin "4") (pinfunction "QE_4") (pintype "output"))
    )
    (net (code "102") (name "Net-(U2-QF)") (class "Default")
      (node (ref "R54") (pin "1") (pinfunction "1_1") (pintype "passive"))
      (node (ref "U2") (pin "5") (pinfunction "QF_5") (pintype "output"))
    )
    (net (code "103") (name "Net-(U2-QG)") (class "Default")
      (node (ref "R55") (pin "1") (pinfunction "1_1") (pintype "passive"))
      (node (ref "U2") (pin "6") (pinfunction "QG_6") (pintype "output"))
    )
    (net (code "104") (name "Net-(U2-QH)") (class "Default")
      (node (ref "R56") (pin "1") (pinfunction "1_1") (pintype "passive"))
      (node (ref "U2") (pin "7") (pinfunction "QH_7") (pintype "output"))
    )
    (net (code "105") (name "Net-(U2-SQH)") (class "Default")
      (node (ref "U2") (pin "9") (pinfunction "SQH_9") (pintype "output"))
      (node (ref "U3") (pin "14") (pinfunction "A_14") (pintype "input"))
    )
    (net (code "106") (name "Net-(U3-QA)") (class "Default")
      (node (ref "R41") (pin "1") (pinfunction "1_1") (pintype "passive"))
      (node (ref "U3") (pin "15") (pinfunction "QA_15") (pintype "output"))
    )
    (net (code "107") (name "Net-(U3-QB)") (class "Default")
      (node (ref "R42") (pin "1") (pinfunction "1_1") (pintype "passive"))
      (node (ref "U3") (pin "1") (pinfunction "QB_1") (pintype "output"))
    )
    (net (code "108") (name "Net-(U3-QC)") (class "Default")
      (node (ref "R43") (pin "1") (pinfunction "1_1") (pintype "passive"))
      (node (ref "U3") (pin "2") (pinfunction "QC_2") (pintype "output"))
    )
    (net (code "109") (name "Net-(U3-QD)") (class "Default")
      (node (ref "R44") (pin "1") (pinfunction "1_1") (pintype "passive"))
      (node (ref "U3") (pin "3") (pinfunction "QD_3") (pintype "output"))
    )
    (net (code "110") (name "Net-(U3-QE)") (class "Default")
      (node (ref "R45") (pin "1") (pinfunction "1_1") (pintype "passive"))
      (node (ref "U3") (pin "4") (pinfunction "QE_4") (pintype "output"))
    )
    (net (code "111") (name "Net-(U3-QF)") (class "Default")
      (node (ref "R46") (pin "1") (pinfunction "1_1") (pintype "passive"))
      (node (ref "U3") (pin "5") (pinfunction "QF_5") (pintype "output"))
    )
    (net (code "112") (name "Net-(U3-QG)") (class "Default")
      (node (ref "R47") (pin "1") (pinfunction "1_1") (pintype "passive"))
      (node (ref "U3") (pin "6") (pinfunction "QG_6") (pintype "output"))
    )
    (net (code "113") (name "Net-(U3-QH)") (class "Default")
      (node (ref "R48") (pin "1") (pinfunction "1_1") (pintype "passive"))
      (node (ref "U3") (pin "7") (pinfunction "QH_7") (pintype "output"))
    )
    (net (code "114") (name "Net-(U3-SQH)") (class "Default")
      (node (ref "U3") (pin "9") (pinfunction "SQH_9") (pintype "output"))
      (node (ref "U4") (pin "14") (pinfunction "A_14") (pintype "input"))
    )
    (net (code "115") (name "Net-(U4-QA)") (class "Default")
      (node (ref "R33") (pin "1") (pinfunction "1_1") (pintype "passive"))
      (node (ref "U4") (pin "15") (pinfunction "QA_15") (pintype "output"))
    )
    (net (code "116") (name "Net-(U4-QB)") (class "Default")
      (node (ref "R34") (pin "1") (pinfunction "1_1") (pintype "passive"))
      (node (ref "U4") (pin "1") (pinfunction "QB_1") (pintype "output"))
    )
    (net (code "117") (name "Net-(U4-QC)") (class "Default")
      (node (ref "R35") (pin "1") (pinfunction "1_1") (pintype "passive"))
      (node (ref "U4") (pin "2") (pinfunction "QC_2") (pintype "output"))
    )
    (net (code "118") (name "Net-(U4-QD)") (class "Default")
      (node (ref "R36") (pin "1") (pinfunction "1_1") (pintype "passive"))
      (node (ref "U4") (pin "3") (pinfunction "QD_3") (pintype "output"))
    )
    (net (code "119") (name "Net-(U4-QE)") (class "Default")
      (node (ref "R37") (pin "1") (pinfunction "1_1") (pintype "passive"))
      (node (ref "U4") (pin "4") (pinfunction "QE_4") (pintype "output"))
    )
    (net (code "120") (name "Net-(U4-QF)") (class "Default")
      (node (ref "R38") (pin "1") (pinfunction "1_1") (pintype "passive"))
      (node (ref "U4") (pin "5") (pinfunction "QF_5") (pintype "output"))
    )
    (net (code "121") (name "Net-(U4-QG)") (class "Default")
      (node (ref "R39") (pin "1") (pinfunction "1_1") (pintype "passive"))
      (node (ref "U4") (pin "6") (pinfunction "QG_6") (pintype "output"))
    )
    (net (code "122") (name "Net-(U4-QH)") (class "Default")
      (node (ref "R40") (pin "1") (pinfunction "1_1") (pintype "passive"))
      (node (ref "U4") (pin "7") (pinfunction "QH_7") (pintype "output"))
    )
    (net (code "123") (name "Net-(U4-SQH)") (class "Default")
      (node (ref "U4") (pin "9") (pinfunction "SQH_9") (pintype "output"))
      (node (ref "U5") (pin "14") (pinfunction "A_14") (pintype "input"))
    )
    (net (code "124") (name "Net-(U5-QA)") (class "Default")
      (node (ref "R25") (pin "1") (pinfunction "1_1") (pintype "passive"))
      (node (ref "U5") (pin "15") (pinfunction "QA_15") (pintype "output"))
    )
    (net (code "125") (name "Net-(U5-QB)") (class "Default")
      (node (ref "R26") (pin "1") (pinfunction "1_1") (pintype "passive"))
      (node (ref "U5") (pin "1") (pinfunction "QB_1") (pintype "output"))
    )
    (net (code "126") (name "Net-(U5-QC)") (class "Default")
      (node (ref "R27") (pin "1") (pinfunction "1_1") (pintype "passive"))
      (node (ref "U5") (pin "2") (pinfunction "QC_2") (pintype "output"))
    )
    (net (code "127") (name "Net-(U5-QD)") (class "Default")
      (node (ref "R28") (pin "1") (pinfunction "1_1") (pintype "passive"))
      (node (ref "U5") (pin "3") (pinfunction "QD_3") (pintype "output"))
    )
    (net (code "128") (name "Net-(U5-QE)") (class "Default")
      (node (ref "R29") (pin "1") (pinfunction "1_1") (pintype "passive"))
      (node (ref "U5") (pin "4") (pinfunction "QE_4") (pintype "output"))
    )
    (net (code "129") (name "Net-(U5-QF)") (class "Default")
      (node (ref "R30") (pin "1") (pinfunction "1_1") (pintype "passive"))
      (node (ref "U5") (pin "5") (pinfunction "QF_5") (pintype "output"))
    )
    (net (code "130") (name "Net-(U5-QG)") (class "Default")
      (node (ref "R31") (pin "1") (pinfunction "1_1") (pintype "passive"))
      (node (ref "U5") (pin "6") (pinfunction "QG_6") (pintype "output"))
    )
    (net (code "131") (name "Net-(U5-QH)") (class "Default")
      (node (ref "R32") (pin "1") (pinfunction "1_1") (pintype "passive"))
      (node (ref "U5") (pin "7") (pinfunction "QH_7") (pintype "output"))
    )
    (net (code "132") (name "Net-(U5-SQH)") (class "Default")
      (node (ref "U5") (pin "9") (pinfunction "SQH_9") (pintype "output"))
      (node (ref "U6") (pin "14") (pinfunction "A_14") (pintype "input"))
    )
    (net (code "133") (name "Net-(U6-QA)") (class "Default")
      (node (ref "R17") (pin "1") (pinfunction "1_1") (pintype "passive"))
      (node (ref "U6") (pin "15") (pinfunction "QA_15") (pintype "output"))
    )
    (net (code "134") (name "Net-(U6-QB)") (class "Default")
      (node (ref "R18") (pin "1") (pinfunction "1_1") (pintype "passive"))
      (node (ref "U6") (pin "1") (pinfunction "QB_1") (pintype "output"))
    )
    (net (code "135") (name "Net-(U6-QC)") (class "Default")
      (node (ref "R19") (pin "1") (pinfunction "1_1") (pintype "passive"))
      (node (ref "U6") (pin "2") (pinfunction "QC_2") (pintype "output"))
    )
    (net (code "136") (name "Net-(U6-QD)") (class "Default")
      (node (ref "R20") (pin "1") (pinfunction "1_1") (pintype "passive"))
      (node (ref "U6") (pin "3") (pinfunction "QD_3") (pintype "output"))
    )
    (net (code "137") (name "Net-(U6-QE)") (class "Default")
      (node (ref "R21") (pin "1") (pinfunction "1_1") (pintype "passive"))
      (node (ref "U6") (pin "4") (pinfunction "QE_4") (pintype "output"))
    )
    (net (code "138") (name "Net-(U6-QF)") (class "Default")
      (node (ref "R22") (pin "1") (pinfunction "1_1") (pintype "passive"))
      (node (ref "U6") (pin "5") (pinfunction "QF_5") (pintype "output"))
    )
    (net (code "139") (name "Net-(U6-QG)") (class "Default")
      (node (ref "R23") (pin "1") (pinfunction "1_1") (pintype "passive"))
      (node (ref "U6") (pin "6") (pinfunction "QG_6") (pintype "output"))
    )
    (net (code "140") (name "Net-(U6-QH)") (class "Default")
      (node (ref "R24") (pin "1") (pinfunction "1_1") (pintype "passive"))
      (node (ref "U6") (pin "7") (pinfunction "QH_7") (pintype "output"))
    )
    (net (code "141") (name "Net-(U6-SQH)") (class "Default")
      (node (ref "U6") (pin "9") (pinfunction "SQH_9") (pintype "output"))
      (node (ref "U7") (pin "14") (pinfunction "A_14") (pintype "input"))
    )
    (net (code "142") (name "Net-(U7-QA)") (class "Default")
      (node (ref "R9") (pin "1") (pinfunction "1_1") (pintype "passive"))
      (node (ref "U7") (pin "15") (pinfunction "QA_15") (pintype "output"))
    )
    (net (code "143") (name "Net-(U7-QB)") (class "Default")
      (node (ref "R10") (pin "1") (pinfunction "1_1") (pintype "passive"))
      (node (ref "U7") (pin "1") (pinfunction "QB_1") (pintype "output"))
    )
    (net (code "144") (name "Net-(U7-QC)") (class "Default")
      (node (ref "R11") (pin "1") (pinfunction "1_1") (pintype "passive"))
      (node (ref "U7") (pin "2") (pinfunction "QC_2") (pintype "output"))
    )
    (net (code "145") (name "Net-(U7-QD)") (class "Default")
      (node (ref "R12") (pin "1") (pinfunction "1_1") (pintype "passive"))
      (node (ref "U7") (pin "3") (pinfunction "QD_3") (pintype "output"))
    )
    (net (code "146") (name "Net-(U7-QE)") (class "Default")
      (node (ref "R13") (pin "1") (pinfunction "1_1") (pintype "passive"))
      (node (ref "U7") (pin "4") (pinfunction "QE_4") (pintype "output"))
    )
    (net (code "147") (name "Net-(U7-QF)") (class "Default")
      (node (ref "R14") (pin "1") (pinfunction "1_1") (pintype "passive"))
      (node (ref "U7") (pin "5") (pinfunction "QF_5") (pintype "output"))
    )
    (net (code "148") (name "Net-(U7-QG)") (class "Default")
      (node (ref "R15") (pin "1") (pinfunction "1_1") (pintype "passive"))
      (node (ref "U7") (pin "6") (pinfunction "QG_6") (pintype "output"))
    )
    (net (code "149") (name "Net-(U7-QH)") (class "Default")
      (node (ref "R16") (pin "1") (pinfunction "1_1") (pintype "passive"))
      (node (ref "U7") (pin "7") (pinfunction "QH_7") (pintype "output"))
    )
    (net (code "150") (name "Net-(U7-SQH)") (class "Default")
      (node (ref "U7") (pin "9") (pinfunction "SQH_9") (pintype "output"))
      (node (ref "U8") (pin "14") (pinfunction "A_14") (pintype "input"))
    )
    (net (code "151") (name "Net-(U8-QA)") (class "Default")
      (node (ref "R1") (pin "1") (pinfunction "1_1") (pintype "passive"))
      (node (ref "U8") (pin "15") (pinfunction "QA_15") (pintype "output"))
    )
    (net (code "152") (name "Net-(U8-QB)") (class "Default")
      (node (ref "R2") (pin "1") (pinfunction "1_1") (pintype "passive"))
      (node (ref "U8") (pin "1") (pinfunction "QB_1") (pintype "output"))
    )
    (net (code "153") (name "Net-(U8-QC)") (class "Default")
      (node (ref "R3") (pin "1") (pinfunction "1_1") (pintype "passive"))
      (node (ref "U8") (pin "2") (pinfunction "QC_2") (pintype "output"))
    )
    (net (code "154") (name "Net-(U8-QD)") (class "Default")
      (node (ref "R4") (pin "1") (pinfunction "1_1") (pintype "passive"))
      (node (ref "U8") (pin "3") (pinfunction "QD_3") (pintype "output"))
    )
    (net (code "155") (name "Net-(U8-QE)") (class "Default")
      (node (ref "R5") (pin "1") (pinfunction "1_1") (pintype "passive"))
      (node (ref "U8") (pin "4") (pinfunction "QE_4") (pintype "output"))
    )
    (net (code "156") (name "Net-(U8-QF)") (class "Default")
      (node (ref "R6") (pin "1") (pinfunction "1_1") (pintype "passive"))
      (node (ref "U8") (pin "5") (pinfunction "QF_5") (pintype "output"))
    )
    (net (code "157") (name "Net-(U8-QG)") (class "Default")
      (node (ref "R7") (pin "1") (pinfunction "1_1") (pintype "passive"))
      (node (ref "U8") (pin "6") (pinfunction "QG_6") (pintype "output"))
    )
    (net (code "158") (name "Net-(U8-QH)") (class "Default")
      (node (ref "R8") (pin "1") (pinfunction "1_1") (pintype "passive"))
      (node (ref "U8") (pin "7") (pinfunction "QH_7") (pintype "output"))
    )
    (net (code "159") (name "unconnected-(J1-Pad3)") (class "Default")
      (node (ref "J1") (pin "3") (pintype "power_in+no_connect"))
    )
    (net (code "160") (name "unconnected-(MD1-CLK-Pad20)") (class "Default")
      (node (ref "MD1") (pin "20") (pinfunction "CLK_20") (pintype "input+no_connect"))
    )
    (net (code "161") (name "unconnected-(MD1-CMD-Pad18)") (class "Default")
      (node (ref "MD1") (pin "18") (pinfunction "CMD_18") (pintype "input+no_connect"))
    )
    (net (code "162") (name "unconnected-(MD1-EN-Pad2)") (class "Default")
      (node (ref "MD1") (pin "2") (pinfunction "EN_2") (pintype "input+no_connect"))
    )
    (net (code "163") (name "unconnected-(MD1-IO0-Pad25)") (class "Default")
      (node (ref "MD1") (pin "25") (pinfunction "IO0_25") (pintype "bidirectional+no_connect"))
    )
    (net (code "164") (name "unconnected-(MD1-IO2-Pad24)") (class "Default")
      (node (ref "MD1") (pin "24") (pinfunction "IO2_24") (pintype "bidirectional+no_connect"))
    )
    (net (code "165") (name "unconnected-(MD1-IO4-Pad26)") (class "Default")
      (node (ref "MD1") (pin "26") (pinfunction "IO4_26") (pintype "bidirectional+no_connect"))
    )
    (net (code "166") (name "unconnected-(MD1-IO5-Pad29)") (class "Default")
      (node (ref "MD1") (pin "29") (pinfunction "IO5_29") (pintype "bidirectional+no_connect"))
    )
    (net (code "167") (name "unconnected-(MD1-IO12-Pad13)") (class "Default")
      (node (ref "MD1") (pin "13") (pinfunction "IO12_13") (pintype "bidirectional+no_connect"))
    )
    (net (code "168") (name "unconnected-(MD1-IO13-Pad15)") (class "Default")
      (node (ref "MD1") (pin "15") (pinfunction "IO13_15") (pintype "bidirectional+no_connect"))
    )
    (net (code "169") (name "unconnected-(MD1-IO14-Pad12)") (class "Default")
      (node (ref "MD1") (pin "12") (pinfunction "IO14_12") (pintype "bidirectional+no_connect"))
    )
    (net (code "170") (name "unconnected-(MD1-IO15-Pad23)") (class "Default")
      (node (ref "MD1") (pin "23") (pinfunction "IO15_23") (pintype "bidirectional+no_connect"))
    )
    (net (code "171") (name "unconnected-(MD1-IO16-Pad27)") (class "Default")
      (node (ref "MD1") (pin "27") (pinfunction "IO16_27") (pintype "bidirectional+no_connect"))
    )
    (net (code "172") (name "unconnected-(MD1-IO17-Pad28)") (class "Default")
      (node (ref "MD1") (pin "28") (pinfunction "IO17_28") (pintype "bidirectional+no_connect"))
    )
    (net (code "173") (name "unconnected-(MD1-IO19-Pad31)") (class "Default")
      (node (ref "MD1") (pin "31") (pinfunction "IO19_31") (pintype "bidirectional+no_connect"))
    )
    (net (code "174") (name "unconnected-(MD1-IO22-Pad36)") (class "Default")
      (node (ref "MD1") (pin "36") (pinfunction "IO22_36") (pintype "bidirectional+no_connect"))
    )
    (net (code "175") (name "unconnected-(MD1-IO25-Pad9)") (class "Default")
      (node (ref "MD1") (pin "9") (pinfunction "IO25_9") (pintype "bidirectional+no_connect"))
    )
    (net (code "176") (name "unconnected-(MD1-IO26-Pad10)") (class "Default")
      (node (ref "MD1") (pin "10") (pinfunction "IO26_10") (pintype "bidirectional+no_connect"))
    )
    (net (code "177") (name "unconnected-(MD1-IO32-Pad7)") (class "Default")
      (node (ref "MD1") (pin "7") (pinfunction "IO32_7") (pintype "bidirectional+no_connect"))
    )
    (net (code "178") (name "unconnected-(MD1-IO33-Pad8)") (class "Default")
      (node (ref "MD1") (pin "8") (pinfunction "IO33_8") (pintype "bidirectional+no_connect"))
    )
    (net (code "179") (name "unconnected-(MD1-IO34-Pad5)") (class "Default")
      (node (ref "MD1") (pin "5") (pinfunction "IO34_5") (pintype "input+no_connect"))
    )
    (net (code "180") (name "unconnected-(MD1-IO35-Pad6)") (class "Default")
      (node (ref "MD1") (pin "6") (pinfunction "IO35_6") (pintype "input+no_connect"))
    )
    (net (code "181") (name "unconnected-(MD1-RXD0-Pad34)") (class "Default")
      (node (ref "MD1") (pin "34") (pinfunction "RXD0_34") (pintype "bidirectional+no_connect"))
    )
    (net (code "182") (name "unconnected-(MD1-SD0-Pad21)") (class "Default")
      (node (ref "MD1") (pin "21") (pinfunction "SD0_21") (pintype "bidirectional+no_connect"))
    )
    (net (code "183") (name "unconnected-(MD1-SD1-Pad22)") (class "Default")
      (node (ref "MD1") (pin "22") (pinfunction "SD1_22") (pintype "bidirectional+no_connect"))
    )
    (net (code "184") (name "unconnected-(MD1-SD2-Pad16)") (class "Default")
      (node (ref "MD1") (pin "16") (pinfunction "SD2_16") (pintype "bidirectional+no_connect"))
    )
    (net (code "185") (name "unconnected-(MD1-SD3-Pad17)") (class "Default")
      (node (ref "MD1") (pin "17") (pinfunction "SD3_17") (pintype "bidirectional+no_connect"))
    )
    (net (code "186") (name "unconnected-(MD1-SENSOR_VN-Pad4)") (class "Default")
      (node (ref "MD1") (pin "4") (pinfunction "SENSOR_VN_4") (pintype "input+no_connect"))
    )
    (net (code "187") (name "unconnected-(MD1-SENSOR_VP-Pad3)") (class "Default")
      (node (ref "MD1") (pin "3") (pinfunction "SENSOR_VP_3") (pintype "input+no_connect"))
    )
    (net (code "188") (name "unconnected-(MD1-TXD0-Pad35)") (class "Default")
      (node (ref "MD1") (pin "35") (pinfunction "TXD0_35") (pintype "bidirectional+no_connect"))
    )
    (net (code "189") (name "unconnected-(MD1-VDD-Pad1)") (class "Default")
      (node (ref "MD1") (pin "1") (pinfunction "VDD_1") (pintype "power_in"))
    )
    (net (code "190") (name "unconnected-(SW1-Pad2)") (class "Default")
      (node (ref "SW1") (pin "2") (pinfunction "2_2") (pintype "passive+no_connect"))
    )
    (net (code "191") (name "unconnected-(SW1-Pad4)") (class "Default")
      (node (ref "SW1") (pin "4") (pinfunction "4_4") (pintype "passive+no_connect"))
    )
    (net (code "192") (name "unconnected-(U8-SQH-Pad9)") (class "Default")
      (node (ref "U8") (pin "9") (pinfunction "SQH_9") (pintype "output+no_connect"))
    )
  )
)
